# Transport_Layer_Security.net
KiCad netlist of a schematic drawn in Altium Designer
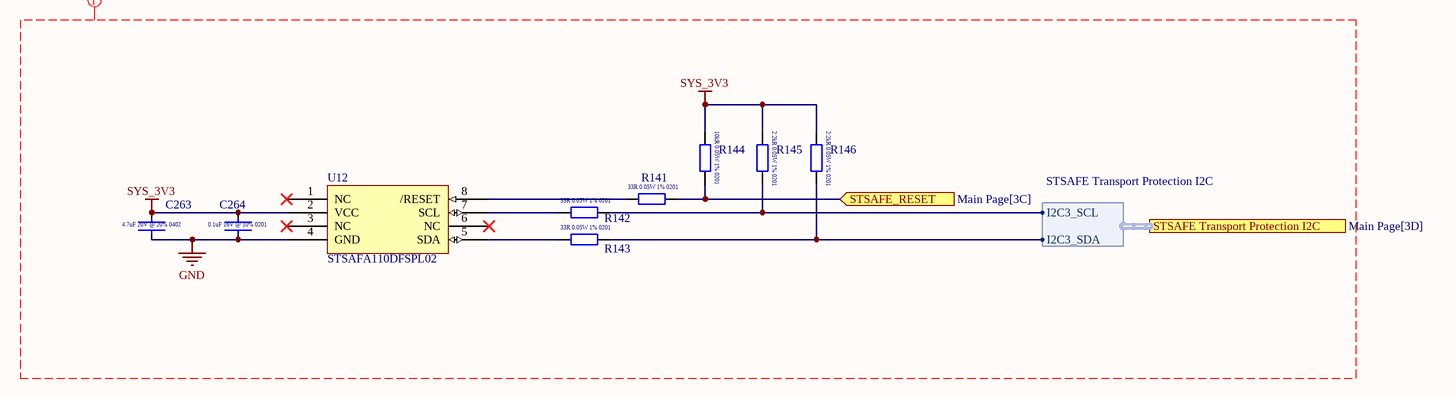
[diagram p0: Transport Layer Security.SchDoc]

(export (version "E")
  (design (tool "Eeschema 10.0.6"))
  (components
    (comp (ref "C263")
      (value "4.7uF")
      (footprint "CAPC1005X06L")
      (description "4.7 µF ±20% 16V Ceramic Capacitor X5R 0402 (1005 Metric)")
      (libsource (lib "Capacitors") (part "CL05A475MO5NUNC"))
    )
    (comp (ref "C264")
      (value "0.1uF")
      (footprint "CAPC0603X03L")
      (libsource (lib "Capacitors") (part "GRM033R61E104KE14J"))
    )
    (comp (ref "R141")
      (value "ERJ-1GNF33R0C")
      (footprint "RESC0603X03L")
      (description "33 Ohms ±1% 0.05W, 1/20W Chip Resistor 0201 (0603 Metric) Thick Film")
      (libsource (lib "Resistors") (part "ERJ-1GNF33R0C"))
    )
    (comp (ref "R142")
      (value "ERJ-1GNF33R0C")
      (footprint "RESC0603X03L")
      (description "33 Ohms ±1% 0.05W, 1/20W Chip Resistor 0201 (0603 Metric) Thick Film")
      (libsource (lib "Resistors") (part "ERJ-1GNF33R0C"))
    )
    (comp (ref "R143")
      (value "ERJ-1GNF33R0C")
      (footprint "RESC0603X03L")
      (description "33 Ohms ±1% 0.05W, 1/20W Chip Resistor 0201 (0603 Metric) Thick Film")
      (libsource (lib "Resistors") (part "ERJ-1GNF33R0C"))
    )
    (comp (ref "R144")
      (value "ERJ-1GNF1002C")
      (footprint "RESC0603X03L")
      (description "10 kOhms ±1% 0.05W, 1/20W Chip Resistor 0201 (0603 Metric) Thick Film")
      (libsource (lib "Resistors") (part "ERJ-1GNF1002C"))
    )
    (comp (ref "R145")
      (value "RC0201FR-072K2L")
      (footprint "RESC0603X03L")
      (description "2.2 kOhms ±1% 0.05W, 1/20W Chip Resistor 0201 (0603 Metric) Moisture Resistant Thick Film")
      (libsource (lib "Resistors") (part "RC0201FR-072K2L"))
    )
    (comp (ref "R146")
      (value "RC0201FR-072K2L")
      (footprint "RESC0603X03L")
      (description "2.2 kOhms ±1% 0.05W, 1/20W Chip Resistor 0201 (0603 Metric) Moisture Resistant Thick Film")
      (libsource (lib "Resistors") (part "RC0201FR-072K2L"))
    )
    (comp (ref "U12")
      (value "STSAFA110DFSPL02")
      (footprint "STSAFE-A110")
      (description "Authentication Chip, IoT Secure Element 8-UFDFPN (2x3)")
      (libsource (lib "Gesturelink Schematic Library") (part "STSAFA110DFSPL02"))
    )
  )
  (nets
    (net (code "5") (name "/STSAFE_RESET") (class "Default")
      (node (ref "R141") (pin "2") (pinfunction "2_2") (pintype "passive"))
      (node (ref "R144") (pin "2") (pinfunction "2_2") (pintype "passive"))
    )
    (net (code "7") (name "GND") (class "Default")
      (node (ref "C263") (pin "1") (pinfunction "1_1") (pintype "passive"))
      (node (ref "C264") (pin "1") (pinfunction "1_1") (pintype "passive"))
      (node (ref "U12") (pin "4") (pinfunction "GND_4") (pintype "power_in"))
    )
    (net (code "8") (name "Net-(R142-Pad2)") (class "Default")
      (node (ref "R142") (pin "2") (pinfunction "2_2") (pintype "passive"))
      (node (ref "R145") (pin "2") (pinfunction "2_2") (pintype "passive"))
    )
    (net (code "9") (name "Net-(R143-Pad2)") (class "Default")
      (node (ref "R143") (pin "2") (pinfunction "2_2") (pintype "passive"))
      (node (ref "R146") (pin "2") (pinfunction "2_2") (pintype "passive"))
    )
    (net (code "10") (name "Net-(U12-SCL)") (class "Default")
      (node (ref "R142") (pin "1") (pinfunction "1_1") (pintype "passive"))
      (node (ref "U12") (pin "7") (pinfunction "SCL_7") (pintype "bidirectional"))
    )
    (net (code "11") (name "Net-(U12-SDA)") (class "Default")
      (node (ref "R143") (pin "1") (pinfunction "1_1") (pintype "passive"))
      (node (ref "U12") (pin "5") (pinfunction "SDA_5") (pintype "bidirectional"))
    )
    (net (code "12") (name "Net-(U12-{slash}RESET)") (class "Default")
      (node (ref "R141") (pin "1") (pinfunction "1_1") (pintype "passive"))
      (node (ref "U12") (pin "8") (pinfunction "/RESET_8") (pintype "input"))
    )
    (net (code "13") (name "SYS_3V3") (class "Default")
      (node (ref "C263") (pin "2") (pinfunction "2_2") (pintype "passive"))
      (node (ref "C264") (pin "2") (pinfunction "2_2") (pintype "passive"))
      (node (ref "R144") (pin "1") (pinfunction "1_1") (pintype "passive"))
      (node (ref "R145") (pin "1") (pinfunction "1_1") (pintype "passive"))
      (node (ref "R146") (pin "1") (pinfunction "1_1") (pintype "passive"))
      (node (ref "U12") (pin "2") (pinfunction "VCC_2") (pintype "power_in"))
    )
    (net (code "14") (name "unconnected-(U12-NC-Pad1)") (class "Default")
      (node (ref "U12") (pin "1") (pinfunction "NC_1") (pintype "passive+no_connect"))
    )
    (net (code "15") (name "unconnected-(U12-NC-Pad3)") (class "Default")
      (node (ref "U12") (pin "3") (pinfunction "NC_3") (pintype "passive+no_connect"))
    )
    (net (code "16") (name "unconnected-(U12-NC-Pad6)") (class "Default")
      (node (ref "U12") (pin "6") (pinfunction "NC_6") (pintype "passive+no_connect"))
    )
  )
)
